# Grove_Bee_Socket_V0_9a.net
KiCad netlist of a schematic drawn in EAGLE
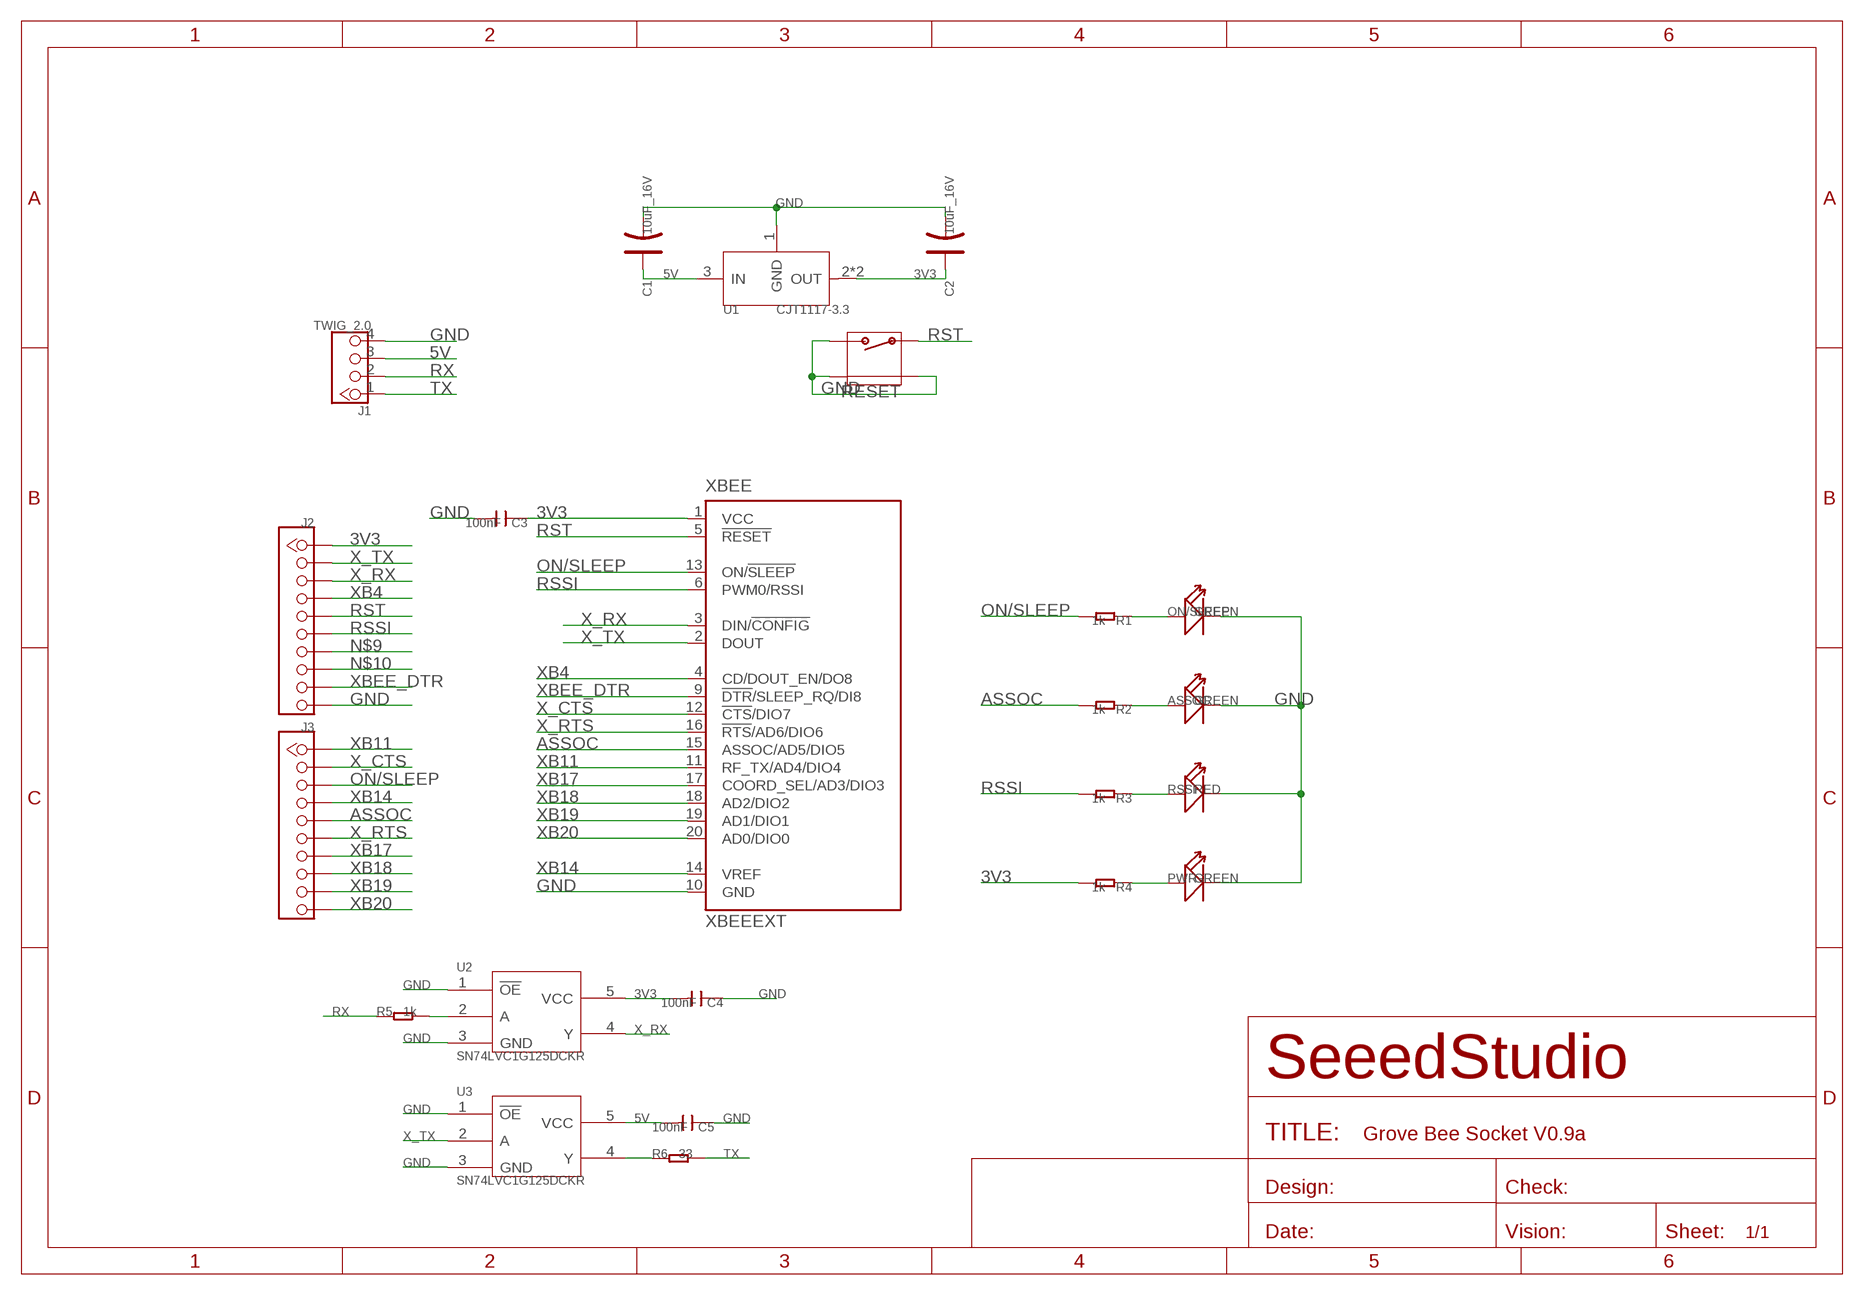
[diagram p0: schematic, sheet 1]

(export (version "E")
  (design (tool "Eeschema 10.0.6"))
  (components
    (comp (ref "ASSOC")
      (value "GREEN")
      (footprint "eagle-import:LED-0603")
      (libsource (lib "eagle-import") (part "LED'0603'"))
    )
    (comp (ref "C1")
      (value "10uF_16V")
      (footprint "eagle-import:AVX-A")
      (libsource (lib "eagle-import") (part "CAP-AVX-A"))
    )
    (comp (ref "C2")
      (value "10uF_16V")
      (footprint "eagle-import:AVX-A")
      (libsource (lib "eagle-import") (part "CAP-AVX-A"))
    )
    (comp (ref "C3")
      (value "100nF")
      (footprint "eagle-import:C0603")
      (libsource (lib "eagle-import") (part "C-0603"))
    )
    (comp (ref "C4")
      (value "100nF")
      (footprint "eagle-import:C0603")
      (libsource (lib "eagle-import") (part "C-0603"))
    )
    (comp (ref "C5")
      (value "100nF")
      (footprint "eagle-import:C0603")
      (libsource (lib "eagle-import") (part "C-0603"))
    )
    (comp (ref "J1")
      (value "TWIG_2.0")
      (footprint "eagle-import:2.0_1X4")
      (libsource (lib "eagle-import") (part "TWIG_2.0"))
    )
    (comp (ref "J2")
      (value "DNP")
      (footprint "eagle-import:CK1X10")
      (libsource (lib "eagle-import") (part "CK1X10DD"))
    )
    (comp (ref "J3")
      (value "DNP")
      (footprint "eagle-import:CK1X10")
      (libsource (lib "eagle-import") (part "CK1X10DD"))
    )
    (comp (ref "ON/SLEEP")
      (value "GREEN")
      (footprint "eagle-import:LED-0603")
      (libsource (lib "eagle-import") (part "LED'0603'"))
    )
    (comp (ref "PWR")
      (value "GREEN")
      (footprint "eagle-import:LED-0603")
      (libsource (lib "eagle-import") (part "LED'0603'"))
    )
    (comp (ref "R1")
      (value "1k")
      (footprint "eagle-import:R0603")
      (libsource (lib "eagle-import") (part "R-0603"))
    )
    (comp (ref "R2")
      (value "1k")
      (footprint "eagle-import:R0603")
      (libsource (lib "eagle-import") (part "R-0603"))
    )
    (comp (ref "R3")
      (value "1k")
      (footprint "eagle-import:R0603")
      (libsource (lib "eagle-import") (part "R-0603"))
    )
    (comp (ref "R4")
      (value "1k")
      (footprint "eagle-import:R0603")
      (libsource (lib "eagle-import") (part "R-0603"))
    )
    (comp (ref "R5")
      (value "1k")
      (footprint "eagle-import:R0603")
      (libsource (lib "eagle-import") (part "R-0603"))
    )
    (comp (ref "R6")
      (value "33")
      (footprint "eagle-import:R0603")
      (libsource (lib "eagle-import") (part "R-0603"))
    )
    (comp (ref "RESET")
      (value "FOR_TEST_ALBERT_V6_BUTTON_4P_SMD")
      (footprint "eagle-import:FOR_TEST_ALBERT_V6_4P-SMD-7X3.5X3.5")
      (libsource (lib "eagle-import") (part "FOR_TEST_ALBERT_V6_BUTTON_4P_SMD"))
    )
    (comp (ref "RSSI")
      (value "RED")
      (footprint "eagle-import:LED-0603")
      (libsource (lib "eagle-import") (part "LED'0603'"))
    )
    (comp (ref "U1")
      (value "CJT1117-3.3")
      (footprint "eagle-import:SOT-223")
      (libsource (lib "eagle-import") (part "LD1117S"))
    )
    (comp (ref "U2")
      (value "SN74LVC1G125DCKR")
      (footprint "eagle-import:SOT353")
      (libsource (lib "eagle-import") (part "SN74LVC1G125DCKR"))
    )
    (comp (ref "U3")
      (value "SN74LVC1G125DCKR")
      (footprint "eagle-import:SOT353")
      (libsource (lib "eagle-import") (part "SN74LVC1G125DCKR"))
    )
    (comp (ref "XBEE")
      (value "XBEEEXT")
      (footprint "eagle-import:XBEE_PLUG")
      (libsource (lib "eagle-import") (part "XBEEEXT"))
    )
  )
  (nets
    (net (code "1") (name "/3V3") (class "Default")
      (node (ref "C2") (pin "+") (pinfunction "+_+") (pintype "passive"))
      (node (ref "C3") (pin "1") (pinfunction "1_1") (pintype "passive"))
      (node (ref "C4") (pin "2") (pinfunction "2_2") (pintype "passive"))
      (node (ref "J2") (pin "1") (pinfunction "1_1") (pintype "bidirectional"))
      (node (ref "R4") (pin "2") (pinfunction "2_2") (pintype "passive"))
      (node (ref "U1") (pin "2") (pinfunction "OUT_2") (pintype "bidirectional"))
      (node (ref "U1") (pin "TER") (pinfunction "OUT_TER") (pintype "bidirectional"))
      (node (ref "U2") (pin "5") (pinfunction "VCC_5") (pintype "bidirectional"))
      (node (ref "XBEE") (pin "1") (pinfunction "VCC_1") (pintype "power_in"))
    )
    (net (code "2") (name "/5V") (class "Default")
      (node (ref "C1") (pin "+") (pinfunction "+_+") (pintype "passive"))
      (node (ref "C5") (pin "2") (pinfunction "2_2") (pintype "passive"))
      (node (ref "J1") (pin "3") (pinfunction "3_3") (pintype "bidirectional"))
      (node (ref "U1") (pin "3") (pinfunction "IN_3") (pintype "bidirectional"))
      (node (ref "U3") (pin "5") (pinfunction "VCC_5") (pintype "bidirectional"))
    )
    (net (code "3") (name "/ASSOC") (class "Default")
      (node (ref "J3") (pin "5") (pinfunction "5_5") (pintype "bidirectional"))
      (node (ref "R2") (pin "2") (pinfunction "2_2") (pintype "passive"))
      (node (ref "XBEE") (pin "15") (pinfunction "ASSOC/AD5/DIO5_15") (pintype "bidirectional"))
    )
    (net (code "4") (name "/GND") (class "Default")
      (node (ref "ASSOC") (pin "-") (pinfunction "-_-") (pintype "passive"))
      (node (ref "C1") (pin "-") (pinfunction "-_-") (pintype "passive"))
      (node (ref "C2") (pin "-") (pinfunction "-_-") (pintype "passive"))
      (node (ref "C3") (pin "2") (pinfunction "2_2") (pintype "passive"))
      (node (ref "C4") (pin "1") (pinfunction "1_1") (pintype "passive"))
      (node (ref "C5") (pin "1") (pinfunction "1_1") (pintype "passive"))
      (node (ref "J1") (pin "4") (pinfunction "4_4") (pintype "bidirectional"))
      (node (ref "J2") (pin "10") (pinfunction "10_10") (pintype "bidirectional"))
      (node (ref "ON/SLEEP") (pin "-") (pinfunction "-_-") (pintype "passive"))
      (node (ref "PWR") (pin "-") (pinfunction "-_-") (pintype "passive"))
      (node (ref "RESET") (pin "2") (pinfunction "2_2") (pintype "bidirectional"))
      (node (ref "RESET") (pin "S1") (pinfunction "S1_S1") (pintype "bidirectional"))
      (node (ref "RESET") (pin "S2") (pinfunction "S2_S2") (pintype "bidirectional"))
      (node (ref "RSSI") (pin "-") (pinfunction "-_-") (pintype "passive"))
      (node (ref "U1") (pin "1") (pinfunction "GND_1") (pintype "bidirectional"))
      (node (ref "U2") (pin "1") (pinfunction "~{OE}_1") (pintype "bidirectional"))
      (node (ref "U2") (pin "3") (pinfunction "GND_3") (pintype "bidirectional"))
      (node (ref "U3") (pin "1") (pinfunction "~{OE}_1") (pintype "bidirectional"))
      (node (ref "U3") (pin "3") (pinfunction "GND_3") (pintype "bidirectional"))
      (node (ref "XBEE") (pin "10") (pinfunction "GND_10") (pintype "bidirectional"))
    )
    (net (code "5") (name "/N$9") (class "Default")
      (node (ref "J2") (pin "7") (pinfunction "7_7") (pintype "bidirectional"))
    )
    (net (code "6") (name "/N$10") (class "Default")
      (node (ref "J2") (pin "8") (pinfunction "8_8") (pintype "bidirectional"))
    )
    (net (code "7") (name "/ON{slash}SLEEP") (class "Default")
      (node (ref "J3") (pin "3") (pinfunction "3_3") (pintype "bidirectional"))
      (node (ref "R1") (pin "2") (pinfunction "2_2") (pintype "passive"))
      (node (ref "XBEE") (pin "13") (pinfunction "ON/~{SLEEP}_13") (pintype "output"))
    )
    (net (code "8") (name "/RSSI") (class "Default")
      (node (ref "J2") (pin "6") (pinfunction "6_6") (pintype "bidirectional"))
      (node (ref "R3") (pin "2") (pinfunction "2_2") (pintype "passive"))
      (node (ref "XBEE") (pin "6") (pinfunction "PWM0/RSSI_6") (pintype "output"))
    )
    (net (code "9") (name "/RST") (class "Default")
      (node (ref "J2") (pin "5") (pinfunction "5_5") (pintype "bidirectional"))
      (node (ref "RESET") (pin "1") (pinfunction "1_1") (pintype "bidirectional"))
      (node (ref "XBEE") (pin "5") (pinfunction "~{RESET}_5") (pintype "input"))
    )
    (net (code "10") (name "/RX") (class "Default")
      (node (ref "J1") (pin "2") (pinfunction "2_2") (pintype "bidirectional"))
      (node (ref "R5") (pin "1") (pinfunction "1_1") (pintype "passive"))
    )
    (net (code "11") (name "/TX") (class "Default")
      (node (ref "J1") (pin "1") (pinfunction "1_1") (pintype "bidirectional"))
      (node (ref "R6") (pin "2") (pinfunction "2_2") (pintype "passive"))
    )
    (net (code "12") (name "/XB4") (class "Default")
      (node (ref "J2") (pin "4") (pinfunction "4_4") (pintype "bidirectional"))
      (node (ref "XBEE") (pin "4") (pinfunction "CD/DOUT_EN/DO8_4") (pintype "output"))
    )
    (net (code "13") (name "/XB11") (class "Default")
      (node (ref "J3") (pin "1") (pinfunction "1_1") (pintype "bidirectional"))
      (node (ref "XBEE") (pin "11") (pinfunction "RF_TX/AD4/DIO4_11") (pintype "bidirectional"))
    )
    (net (code "14") (name "/XB14") (class "Default")
      (node (ref "J3") (pin "4") (pinfunction "4_4") (pintype "bidirectional"))
      (node (ref "XBEE") (pin "14") (pinfunction "VREF_14") (pintype "input"))
    )
    (net (code "15") (name "/XB17") (class "Default")
      (node (ref "J3") (pin "7") (pinfunction "7_7") (pintype "bidirectional"))
      (node (ref "XBEE") (pin "17") (pinfunction "COORD_SEL/AD3/DIO3_17") (pintype "bidirectional"))
    )
    (net (code "16") (name "/XB18") (class "Default")
      (node (ref "J3") (pin "8") (pinfunction "8_8") (pintype "bidirectional"))
      (node (ref "XBEE") (pin "18") (pinfunction "AD2/DIO2_18") (pintype "bidirectional"))
    )
    (net (code "17") (name "/XB19") (class "Default")
      (node (ref "J3") (pin "9") (pinfunction "9_9") (pintype "bidirectional"))
      (node (ref "XBEE") (pin "19") (pinfunction "AD1/DIO1_19") (pintype "bidirectional"))
    )
    (net (code "18") (name "/XB20") (class "Default")
      (node (ref "J3") (pin "10") (pinfunction "10_10") (pintype "bidirectional"))
      (node (ref "XBEE") (pin "20") (pinfunction "AD0/DIO0_20") (pintype "bidirectional"))
    )
    (net (code "19") (name "/XBEE_DTR") (class "Default")
      (node (ref "J2") (pin "9") (pinfunction "9_9") (pintype "bidirectional"))
      (node (ref "XBEE") (pin "9") (pinfunction "~{DTR}/SLEEP_RQ/DI8_9") (pintype "bidirectional"))
    )
    (net (code "20") (name "/X_CTS") (class "Default")
      (node (ref "J3") (pin "2") (pinfunction "2_2") (pintype "bidirectional"))
      (node (ref "XBEE") (pin "12") (pinfunction "~{CTS}/DIO7_12") (pintype "bidirectional"))
    )
    (net (code "21") (name "/X_RTS") (class "Default")
      (node (ref "J3") (pin "6") (pinfunction "6_6") (pintype "bidirectional"))
      (node (ref "XBEE") (pin "16") (pinfunction "~{RTS}/AD6/DIO6_16") (pintype "bidirectional"))
    )
    (net (code "22") (name "/X_RX") (class "Default")
      (node (ref "J2") (pin "3") (pinfunction "3_3") (pintype "bidirectional"))
      (node (ref "U2") (pin "4") (pinfunction "Y_4") (pintype "bidirectional"))
      (node (ref "XBEE") (pin "3") (pinfunction "DIN/~{CONFIG}_3") (pintype "input"))
    )
    (net (code "23") (name "/X_TX") (class "Default")
      (node (ref "J2") (pin "2") (pinfunction "2_2") (pintype "bidirectional"))
      (node (ref "U3") (pin "2") (pinfunction "A_2") (pintype "bidirectional"))
      (node (ref "XBEE") (pin "2") (pinfunction "DOUT_2") (pintype "output"))
    )
    (net (code "24") (name "Net-(ASSOC-Pad+)") (class "Default")
      (node (ref "ASSOC") (pin "+") (pinfunction "+_+") (pintype "passive"))
      (node (ref "R2") (pin "1") (pinfunction "1_1") (pintype "passive"))
    )
    (net (code "25") (name "Net-(ON/SLEEP-Pad+)") (class "Default")
      (node (ref "ON/SLEEP") (pin "+") (pinfunction "+_+") (pintype "passive"))
      (node (ref "R1") (pin "1") (pinfunction "1_1") (pintype "passive"))
    )
    (net (code "26") (name "Net-(PWR-Pad+)") (class "Default")
      (node (ref "PWR") (pin "+") (pinfunction "+_+") (pintype "passive"))
      (node (ref "R4") (pin "1") (pinfunction "1_1") (pintype "passive"))
    )
    (net (code "27") (name "Net-(R3-Pad1)") (class "Default")
      (node (ref "R3") (pin "1") (pinfunction "1_1") (pintype "passive"))
      (node (ref "RSSI") (pin "+") (pinfunction "+_+") (pintype "passive"))
    )
    (net (code "28") (name "Net-(U2-A)") (class "Default")
      (node (ref "R5") (pin "2") (pinfunction "2_2") (pintype "passive"))
      (node (ref "U2") (pin "2") (pinfunction "A_2") (pintype "bidirectional"))
    )
    (net (code "29") (name "Net-(U3-Y)") (class "Default")
      (node (ref "R6") (pin "1") (pinfunction "1_1") (pintype "passive"))
      (node (ref "U3") (pin "4") (pinfunction "Y_4") (pintype "bidirectional"))
    )
  )
)
